# Power.net
KiCad netlist of a schematic drawn in Altium Designer
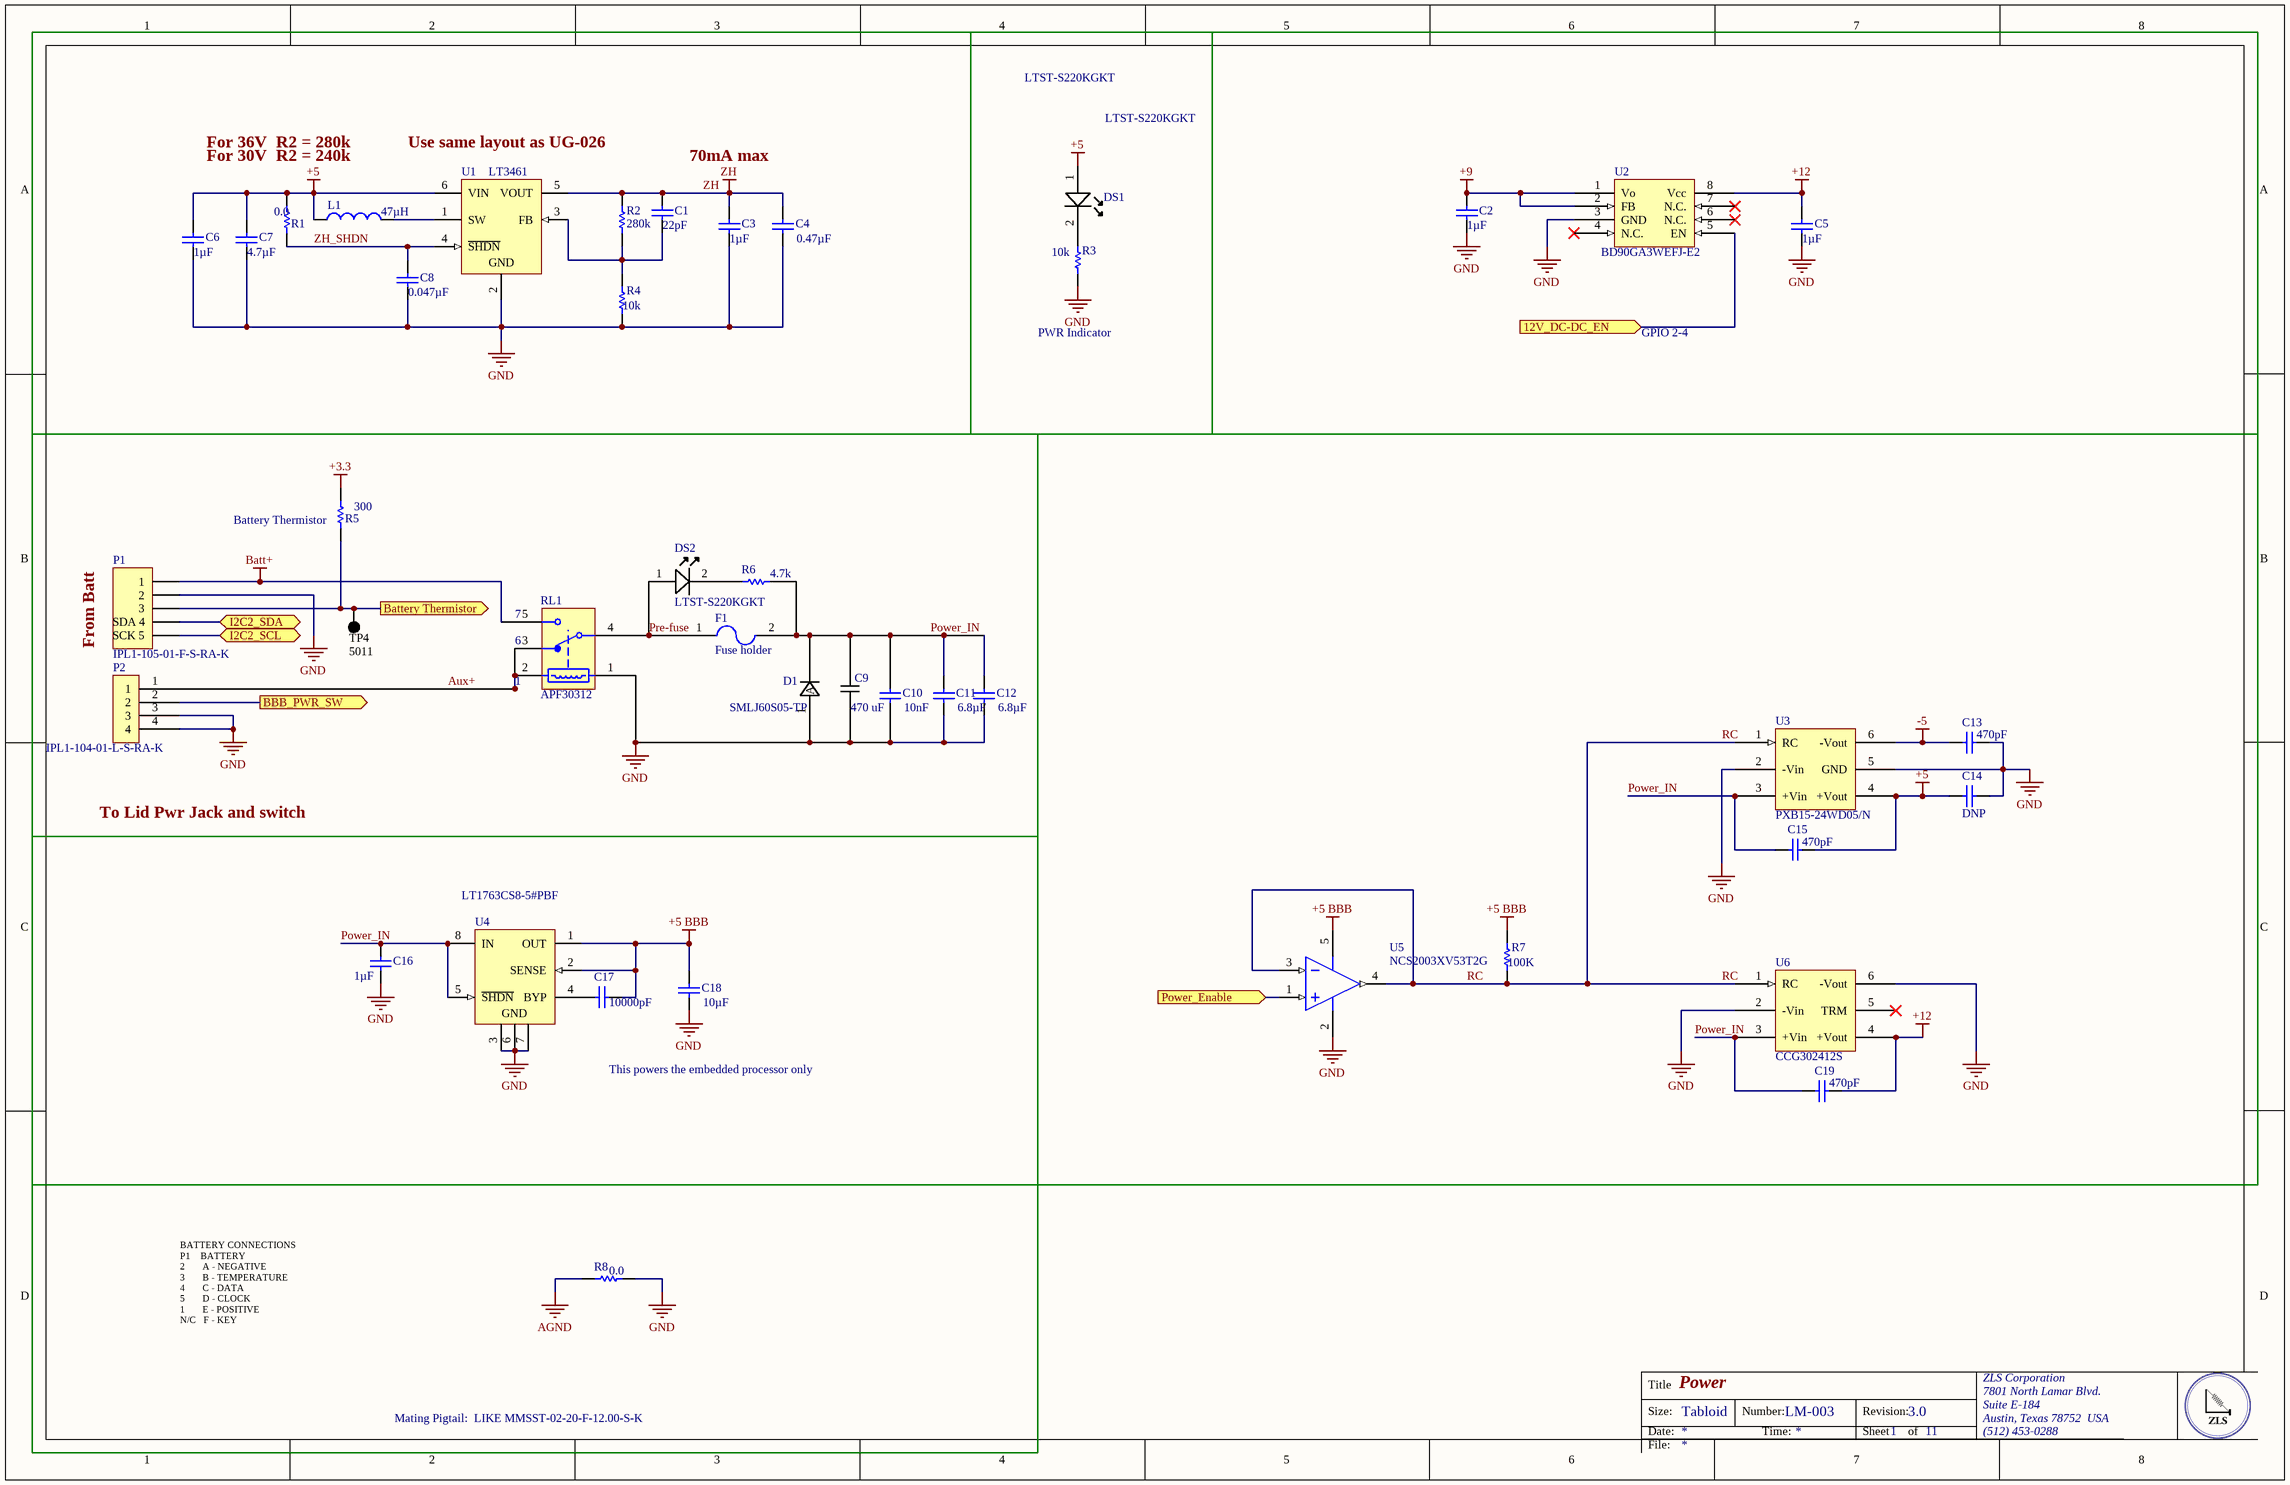
[diagram p0: Power.SchDoc]

(export (version "E")
  (design (tool "Eeschema 10.0.6"))
  (components
    (comp (ref "C1")
      (value "CAP CER 22PF 50V X7R 0603")
      (footprint "CAPC0603(1608)100_N")
      (fields
        (field (name "MANUFACTURER") "AVX Corporation")
        (field (name "MANUFACTURER PART NUMBER") "06035C220JAT2A")
        (field (name "CAPACITANCE") "22pF")
        (field (name "TOLERANCE") "±5%")
      )
      (libsource (lib "Altium Content Vault") (part "CMP-1035-00578-1"))
    )
    (comp (ref "C2")
      (value "CAP CER 1UF 50V X7R 1210")
      (footprint "CAPC1206(3216)130_N")
      (fields
        (field (name "MANUFACTURER") "Murata Electronics North America")
        (field (name "MANUFACTURER PART NUMBER") "GRM32RR71H105KA01L")
        (field (name "CAPACITANCE") "1µF")
        (field (name "TOLERANCE") "±10%")
      )
      (libsource (lib "Altium Content Vault") (part "CMP-1037-04913-1"))
    )
    (comp (ref "C3")
      (value "CAP CER 1UF 50V X7R 1210")
      (footprint "CAPC1210(3225)100_N")
      (fields
        (field (name "MANUFACTURER") "Taiyo Yuden")
        (field (name "MANUFACTURER PART NUMBER") "UMK325B7105KH-T")
        (field (name "CAPACITANCE") "1µF")
        (field (name "TOLERANCE") "±10%")
      )
      (libsource (lib "Altium Content Vault") (part "CMP-1038-01123-1"))
    )
    (comp (ref "C4")
      (value "CAP CER 0.47UF 50V X7R 1206")
      (footprint "CAPC1206(3216)190_N")
      (fields
        (field (name "MANUFACTURER") "Taiyo Yuden")
        (field (name "MANUFACTURER PART NUMBER") "UMK316B7474KL-T")
        (field (name "CAPACITANCE") "0.47µF")
        (field (name "TOLERANCE") "±10%")
      )
      (libsource (lib "Altium Content Vault") (part "CMP-1037-04570-1"))
    )
    (comp (ref "C5")
      (value "CAP CER 1UF 50V X7R 1210")
      (footprint "CAPC1206(3216)130_N")
      (fields
        (field (name "MANUFACTURER") "Murata Electronics North America")
        (field (name "MANUFACTURER PART NUMBER") "GRM32RR71H105KA01L")
        (field (name "CAPACITANCE") "1µF")
        (field (name "TOLERANCE") "±10%")
      )
      (libsource (lib "Altium Content Vault") (part "CMP-1037-04913-1"))
    )
    (comp (ref "C6")
      (value "CAP CER 1UF 16V X7R 0805")
      (footprint "CAPC0805(2012)145_N")
      (fields
        (field (name "MANUFACTURER") "Taiyo Yuden")
        (field (name "MANUFACTURER PART NUMBER") "EMK212B7105KG-T")
        (field (name "CAPACITANCE") "1µF")
        (field (name "TOLERANCE") "±10%")
      )
      (libsource (lib "Altium Content Vault") (part "CMP-1036-04795-1"))
    )
    (comp (ref "C7")
      (value "CAP CER 4.7UF 16V X7R 1206")
      (footprint "CAPC1206(3216)130_N")
      (fields
        (field (name "MANUFACTURER") "Taiyo Yuden")
        (field (name "MANUFACTURER PART NUMBER") "EMK316B7475KL-T")
        (field (name "CAPACITANCE") "4.7µF")
        (field (name "TOLERANCE") "±10%")
      )
      (libsource (lib "Altium Content Vault") (part "CMP-1037-04913-1"))
    )
    (comp (ref "C8")
      (value "CAP CER 0.047UF 16V X7R 0603")
      (footprint "CAPC0805(2012)145_N")
      (fields
        (field (name "MANUFACTURER") "Murata Electronics North America")
        (field (name "MANUFACTURER PART NUMBER") "GRM188R71C473KA01D")
        (field (name "CAPACITANCE") "0.047µF")
        (field (name "TOLERANCE") "±10%")
      )
      (libsource (lib "Altium Content Vault") (part "CMP-1036-04795-1"))
    )
    (comp (ref "C9")
      (value "Aluminum Electrolytic Capacitors - Leaded 16V 470uF 20%")
      (footprint "RAD-0.1")
      (fields (field (name "CAPACITANCE") "470 uF") (field (name "TOLERANCE") "20 %"))
      (libsource (lib "*") (part "CAP B"))
    )
    (comp (ref "C10")
      (value "CAP CER 10000PF 50V X7R 0805")
      (footprint "CAPC0805(2012)145_N")
      (fields
        (field (name "MANUFACTURER") "Kemet")
        (field (name "MANUFACTURER PART NUMBER") "C0805F103K5RACTU")
        (field (name "CAPACITANCE") "10nF")
        (field (name "TOLERANCE") "10%")
      )
      (libsource (lib "Altium Content Vault") (part "CMP-1036-04795-1"))
    )
    (comp (ref "C11")
      (value "CAP CER 6.8UF 50V X5R 1206")
      (footprint "CAPC1210(3225)100_L")
      (fields
        (field (name "MANUFACTURER") "TDK Corporation")
        (field (name "MANUFACTURER PART NUMBER") "C3216X5R1H685K160AB")
        (field (name "CAPACITANCE") "6.8µF")
        (field (name "TOLERANCE") "±10%")
      )
      (libsource (lib "Altium Content Vault") (part "CMP-1038-00632-1"))
    )
    (comp (ref "C12")
      (value "CAP CER 6.8UF 50V X5R 1206")
      (footprint "CAPC1210(3225)100_L")
      (fields
        (field (name "MANUFACTURER") "TDK Corporation")
        (field (name "MANUFACTURER PART NUMBER") "C3216X5R1H685K160AB")
        (field (name "CAPACITANCE") "6.8µF")
        (field (name "TOLERANCE") "±10%")
      )
      (libsource (lib "Altium Content Vault") (part "CMP-1038-00632-1"))
    )
    (comp (ref "C13")
      (value "CAP CER 470PF 3KV X7R 1812")
      (footprint "CAPC1812(4532)230_M")
      (fields
        (field (name "MANUFACTURER") "Kemet")
        (field (name "MANUFACTURER PART NUMBER") "C1812C471KHRACTU")
        (field (name "CAPACITANCE") "470pF")
        (field (name "TOLERANCE") "10%")
      )
      (libsource (lib "Altium Content Vault") (part "CMP-1040-00561-1"))
    )
    (comp (ref "C14")
      (value "DNP")
      (footprint "CAPC1812(4532)230_M")
      (description "CAP CER 470PF 3KV X7R 1812")
      (fields
        (field (name "MANUFACTURER") "Kemet")
        (field (name "MANUFACTURER PART NUMBER") "C1812C471KHRACTU")
      )
      (libsource (lib "Altium Content Vault") (part "CMP-1040-00561-1"))
    )
    (comp (ref "C15")
      (value "CAP CER 470PF 3KV X7R 1812")
      (footprint "CAPC1812(4532)230_M")
      (fields
        (field (name "MANUFACTURER") "Kemet")
        (field (name "MANUFACTURER PART NUMBER") "C1812C471KHRACTU")
        (field (name "CAPACITANCE") "470pF")
        (field (name "TOLERANCE") "10%")
      )
      (libsource (lib "Altium Content Vault") (part "CMP-1040-00561-1"))
    )
    (comp (ref "C16")
      (value "CAP CER 1UF 50V X7R 1210")
      (footprint "CAPC1210(3225)100_L")
      (fields
        (field (name "MANUFACTURER") "Murata Electronics North America")
        (field (name "MANUFACTURER PART NUMBER") "GRM32RR71H105KA01L")
        (field (name "CAPACITANCE") "1µF")
        (field (name "TOLERANCE") "±10%")
      )
      (libsource (lib "Altium Content Vault") (part "CMP-1038-00632-1"))
    )
    (comp (ref "C17")
      (value "CAP CER 10000PF 25V X7R 0805")
      (footprint "CAPC0805(2012)145_N")
      (fields
        (field (name "MANUFACTURER") "Murata Electronics North America")
        (field (name "MANUFACTURER PART NUMBER") "GRM216R71E103KA01D")
        (field (name "CAPACITANCE") "10000pF")
        (field (name "TOLERANCE") "±10%")
      )
      (libsource (lib "Altium Content Vault") (part "CMP-1036-04795-1"))
    )
    (comp (ref "C18")
      (value "CAP CER 10UF 10V X7R 0805")
      (footprint "CAPC0805(2012)145_N")
      (fields
        (field (name "MANUFACTURER") "Murata Electronics North America")
        (field (name "MANUFACTURER PART NUMBER") "GCM21BR71A106KE22L")
        (field (name "CAPACITANCE") "10µF")
        (field (name "TOLERANCE") "±10%")
      )
      (libsource (lib "Altium Content Vault") (part "CMP-1036-04795-1"))
    )
    (comp (ref "C19")
      (value "CAP CER 470PF 3KV X7R 1812")
      (footprint "CAPC1812(4532)230_M")
      (fields
        (field (name "MANUFACTURER") "Kemet")
        (field (name "MANUFACTURER PART NUMBER") "C1812C471KHRACTU")
        (field (name "CAPACITANCE") "470pF")
        (field (name "TOLERANCE") "10%")
      )
      (libsource (lib "Altium Content Vault") (part "CMP-1040-00561-1"))
    )
    (comp (ref "D1")
      (value "DIODE GEN PURP 50V 6A DO214AB")
      (footprint "DO-214AB")
      (fields
        (field (name "MANUFACTURER") "Micro Commercial Co")
        (field (name "MANUFACTURER PART NUMBER") "SMLJ60S05-TP")
      )
      (libsource (lib "*") (part "DIODE A/K A"))
    )
    (comp (ref "DS1")
      (value "Lite-On LTST-S220KGKT Green LED, 571 nm 2012 (0805) Side View, Rectangle Lens SMD package")
      (footprint "0805C_L")
      (fields
        (field (name "MANUFACTURER") "Vishay / Lite-On")
        (field (name "MANUFACTURER PART NUMBER") "LTST-S220KGKT")
      )
      (libsource (lib "*") (part "LED A/K"))
    )
    (comp (ref "DS2")
      (value "Lite-On LTST-S220KGKT Green LED, 571 nm 2012 (0805) Side View, Rectangle Lens SMD package")
      (footprint "0805C_L")
      (fields
        (field (name "MANUFACTURER") "Vishay / Lite-On")
        (field (name "MANUFACTURER PART NUMBER") "LTST-S220KGKT")
      )
      (libsource (lib "*") (part "LED A/K"))
    )
    (comp (ref "F1")
      (value "Fuse holder")
      (footprint "01530007Z")
      (description "FUSE HOLDER BLADE 32V 15A PCB")
      (fields (field (name "VOLTAGE") "32V"))
      (libsource (lib "Miscellaneous Devices") (part "Fuse 2"))
    )
    (comp (ref "L1")
      (value "FIXED IND 47UH 170MA 1.3 OHM SMD")
      (footprint "0402-A")
      (fields (field (name "INDUCTANCE") "47µH") (field (name "TOLERANCE") "±10%"))
      (libsource (lib "Miscellaneous Devices") (part "Inductor"))
    )
    (comp (ref "P1")
      (value "IPL1-105-01-F-S-RA-K")
      (footprint "IPL1-105-1")
      (description "Header, 5-Pin, Right Angle")
      (libsource (lib "Miscellaneous Connectors") (part "Header 5H"))
    )
    (comp (ref "P2")
      (value "IPL1-104-01-L-S-RA-K")
      (footprint "IPL1-104-01")
      (description ".100 TERMINAL ASSY")
      (libsource (lib "ZLS_LIB") (part "53047-0410"))
    )
    (comp (ref "R1")
      (value "RES SMD 0.0 OHM JUMPER 1/8W 0805")
      (footprint "RESC0805(2012)_M")
      (fields
        (field (name "MANUFACTURER") "Vishay Dale")
        (field (name "MANUFACTURER PART NUMBER") "CRCW08050000Z0EA")
        (field (name "RESISTANCE (OHMS)") "0.0")
        (field (name "TOLERANCE") "Jumper")
      )
      (libsource (lib "Altium Content Vault") (part "CMP-1013-00017-1"))
    )
    (comp (ref "R2")
      (value "RES SMD 280K OHM 1% 1/8W 0805")
      (footprint "RESC0805(2012)_M")
      (fields
        (field (name "MANUFACTURER") "Vishay Dale")
        (field (name "MANUFACTURER PART NUMBER") "CRCW0805280KFKEA")
        (field (name "RESISTANCE (OHMS)") "280k")
        (field (name "TOLERANCE") "±1%")
      )
      (libsource (lib "Altium Content Vault") (part "CMP-1013-00017-1"))
    )
    (comp (ref "R3")
      (value "RES SMD 10K OHM 1% 1/8W 0805")
      (footprint "RESC0805(2012)_M")
      (fields
        (field (name "MANUFACTURER") "Vishay Dale")
        (field (name "MANUFACTURER PART NUMBER") "CRCW080510K0FKTA")
        (field (name "RESISTANCE (OHMS)") "10k")
        (field (name "TOLERANCE") "±1%")
      )
      (libsource (lib "Altium Content Vault") (part "CMP-1013-00017-1"))
    )
    (comp (ref "R4")
      (value "RES SMD 10K OHM 1% 1/8W 0805")
      (footprint "RESC0805(2012)_M")
      (fields
        (field (name "MANUFACTURER") "Yageo")
        (field (name "MANUFACTURER PART NUMBER") "RC0805FR-0710KL")
        (field (name "RESISTANCE (OHMS)") "10k")
        (field (name "TOLERANCE") "±1%")
      )
      (libsource (lib "Altium Content Vault") (part "CMP-1013-00017-1"))
    )
    (comp (ref "R5")
      (value "300K 5% 0805(2012)")
      (footprint "RESC0805(2012)_M")
      (description "300K 0.125W 5% 0805 (2012 Metric)  SMD")
      (fields
        (field (name "MANUFACTURER") "Vishay Dale")
        (field (name "MANUFACTURER PART NUMBER") "CRCW0805300RFKEA")
        (field (name "RESISTANCE (OHMS)") "300")
      )
      (libsource (lib "Altium Content Vault") (part "CMP-1013-00133-1"))
    )
    (comp (ref "R6")
      (value "RES SMD 4.7K OHM 1% 1/8W 0805")
      (footprint "RESC0805(2012)_M")
      (fields
        (field (name "MANUFACTURER") "Vishay Dale")
        (field (name "MANUFACTURER PART NUMBER") "CRCW08054K70FKEA")
        (field (name "RESISTANCE (OHMS)") "4.7k")
        (field (name "TOLERANCE") "±1%")
      )
      (libsource (lib "Altium Content Vault") (part "CMP-1013-00017-1"))
    )
    (comp (ref "R7")
      (value "RES SMD 100K OHM 1% 1/8W 0805")
      (footprint "RESC0805(2012)_M")
      (fields
        (field (name "MANUFACTURER") "Vishay")
        (field (name "MANUFACTURER PART NUMBER") "CRCW0805100KFKEA")
        (field (name "TOLERANCE") "1%")
        (field (name "RESISTANCE") "100K")
      )
      (libsource (lib "Altium Content Vault") (part "CMP-1013-00017-1"))
    )
    (comp (ref "R8")
      (value "RES SMD 0.0 OHM JUMPER 1/8W 0805")
      (footprint "RESC0805(2012)_M")
      (fields
        (field (name "MANUFACTURER") "Vishay Dale")
        (field (name "MANUFACTURER PART NUMBER") "CRCW08050000Z0EA")
        (field (name "RESISTANCE (OHMS)") "0.0")
        (field (name "TOLERANCE") "Jumper")
      )
      (libsource (lib "Altium Content Vault") (part "CMP-1013-00017-1"))
    )
    (comp (ref "RL1")
      (value "APF30312")
      (footprint "PNSC-PF-5-2800x500x1500_V")
      (fields (field (name "MANUFACTURER") "Panasonic"))
      (libsource (lib "Altium Content Vault") (part "CMP-1503-00270-1"))
    )
    (comp (ref "TP4")
      (value "5011")
      (footprint "KSTN-5011_V")
      (description "Test Point, Black, Through Hole, RoHS, Bulk")
      (fields (field (name "MANUFACTURER") "Keystone"))
      (libsource (lib "Altium Content Vault") (part "CMP-1672-00003-4"))
    )
    (comp (ref "U1")
      (value "LT3461")
      (footprint "LT-S6-6-TSOT-23_N")
      (description "IC REG BOOST ADJ 0.3A TSOT23-6")
      (libsource (lib "Altium Content Vault") (part "CMP-0491-01698-1"))
    )
    (comp (ref "U2")
      (value "BD90GA3WEFJ-E2")
      (footprint "TSOP127P600X100-8N")
      (description "IC REG LDO 9V 0.3A 8HTSOP-J")
      (fields
        (field (name "MANUFACTURER") "Rohm Semiconductor")
        (field (name "MANUFACTURER PART NUMBER") "BD90GA3WEFJ-E2")
      )
      (libsource (lib "ZLS_Schematic_lib") (part "BD90GA3WEFJ-E2"))
    )
    (comp (ref "U3")
      (value "PXB15-24WD05/N")
      (footprint "PXB15-24WD05/N")
      (description "IC CONV DC-DC 15W DUAL 5V PCB")
      (libsource (lib "ZLS_LIB") (part "CCG302412S"))
    )
    (comp (ref "U4")
      (value "LT1763CS8-5#PBF")
      (footprint "LT-S8-8_M")
      (fields (field (name "MANUFACTURER") "Linear Technology"))
      (libsource (lib "Altium Content Vault") (part "LT-LT1763-S8-8"))
    )
    (comp (ref "U5")
      (value "NCS2003XV53T2G")
      (footprint "ONSC-SOT-553-5-463B_V")
      (fields (field (name "MANUFACTURER") "On Semiconductor"))
      (libsource (lib "Altium Content Vault") (part "ONSC-NCS200X-5"))
    )
    (comp (ref "U6")
      (value "CCG302412S")
      (footprint "CCG30")
      (description "DC/DC CONVERTER 12V 2.5A PCB")
      (libsource (lib "") (part "CCG302412S_1"))
    )
  )
  (nets
    (net (code "1") (name "+3.3") (class "Default")
      (node (ref "R5") (pin "2") (pinfunction "2_2") (pintype "passive"))
    )
    (net (code "2") (name "+5") (class "Default")
      (node (ref "C14") (pin "1") (pinfunction "1_1") (pintype "passive"))
      (node (ref "C15") (pin "2") (pinfunction "2_2") (pintype "passive"))
      (node (ref "C6") (pin "2") (pinfunction "2_2") (pintype "passive"))
      (node (ref "C7") (pin "2") (pinfunction "2_2") (pintype "passive"))
      (node (ref "DS1") (pin "1") (pinfunction "A_1") (pintype "passive"))
      (node (ref "L1") (pin "1") (pinfunction "1_1") (pintype "passive"))
      (node (ref "R1") (pin "1") (pinfunction "1_1") (pintype "passive"))
      (node (ref "U1") (pin "6") (pinfunction "VIN_6") (pintype "power_in"))
      (node (ref "U3") (pin "4") (pinfunction "+Vout_4") (pintype "power_in"))
    )
    (net (code "3") (name "+5 BBB") (class "Default")
      (node (ref "C17") (pin "1") (pinfunction "1_1") (pintype "passive"))
      (node (ref "C18") (pin "2") (pinfunction "2_2") (pintype "passive"))
      (node (ref "R7") (pin "1") (pinfunction "1_1") (pintype "passive"))
      (node (ref "U4") (pin "1") (pinfunction "OUT_1") (pintype "power_in"))
      (node (ref "U4") (pin "2") (pinfunction "SENSE_2") (pintype "input"))
      (node (ref "U5") (pin "5") (pinfunction "VDD_5") (pintype "power_in"))
    )
    (net (code "4") (name "+9") (class "Default")
      (node (ref "C2") (pin "2") (pinfunction "2_2") (pintype "passive"))
      (node (ref "U2") (pin "1") (pinfunction "Vo_1") (pintype "power_in"))
      (node (ref "U2") (pin "2") (pinfunction "FB_2") (pintype "input"))
    )
    (net (code "5") (name "+12") (class "Default")
      (node (ref "C19") (pin "2") (pinfunction "2_2") (pintype "passive"))
      (node (ref "C5") (pin "2") (pinfunction "2_2") (pintype "passive"))
      (node (ref "U2") (pin "8") (pinfunction "Vcc_8") (pintype "power_in"))
      (node (ref "U6") (pin "4") (pinfunction "+Vout_4") (pintype "power_in"))
    )
    (net (code "6") (name "-5") (class "Default")
      (node (ref "C13") (pin "1") (pinfunction "1_1") (pintype "passive"))
      (node (ref "U3") (pin "6") (pinfunction "-Vout_6") (pintype "power_in"))
    )
    (net (code "7") (name "/12V_DC-DC_EN") (class "Default")
      (node (ref "U2") (pin "5") (pinfunction "EN_5") (pintype "input"))
    )
    (net (code "8") (name "/Aux+") (class "Default")
      (node (ref "P2") (pin "1") (pinfunction "1_1") (pintype "passive"))
      (node (ref "RL1") (pin "2") (pinfunction "2_2") (pintype "passive"))
      (node (ref "RL1") (pin "3") (pinfunction "NC_3") (pintype "passive"))
    )
    (net (code "9") (name "/BBB_PWR_SW") (class "Default")
      (node (ref "P2") (pin "2") (pinfunction "2_2") (pintype "passive"))
    )
    (net (code "10") (name "/Battery Thermistor") (class "Default")
      (node (ref "P1") (pin "3") (pinfunction "3_3") (pintype "passive"))
      (node (ref "R5") (pin "1") (pinfunction "1_1") (pintype "passive"))
      (node (ref "TP4") (pin "1") (pinfunction "1_1") (pintype "passive"))
    )
    (net (code "11") (name "/I2C2_SCL") (class "Default")
      (node (ref "P1") (pin "5") (pinfunction "SCK_5_5") (pintype "passive"))
    )
    (net (code "12") (name "/I2C2_SDA") (class "Default")
      (node (ref "P1") (pin "4") (pinfunction "SDA_4_4") (pintype "passive"))
    )
    (net (code "13") (name "/Power_Enable") (class "Default")
      (node (ref "U5") (pin "1") (pinfunction "IN+_1") (pintype "input"))
    )
    (net (code "14") (name "/Power_IN") (class "Default")
      (node (ref "C10") (pin "2") (pinfunction "2_2") (pintype "passive"))
      (node (ref "C11") (pin "2") (pinfunction "2_2") (pintype "passive"))
      (node (ref "C12") (pin "2") (pinfunction "2_2") (pintype "passive"))
      (node (ref "C15") (pin "1") (pinfunction "1_1") (pintype "passive"))
      (node (ref "C16") (pin "2") (pinfunction "2_2") (pintype "passive"))
      (node (ref "C19") (pin "1") (pinfunction "1_1") (pintype "passive"))
      (node (ref "C9") (pin "1") (pinfunction "1_1") (pintype "passive"))
      (node (ref "D1") (pin "2") (pinfunction "K_2") (pintype "passive"))
      (node (ref "F1") (pin "2") (pinfunction "2_2") (pintype "passive"))
      (node (ref "R6") (pin "1") (pinfunction "1_1") (pintype "passive"))
      (node (ref "U3") (pin "3") (pinfunction "+Vin_3") (pintype "power_in"))
      (node (ref "U4") (pin "5") (pinfunction "~{SHDN}_5") (pintype "input"))
      (node (ref "U4") (pin "8") (pinfunction "IN_8") (pintype "power_in"))
      (node (ref "U6") (pin "3") (pinfunction "+Vin_3") (pintype "passive"))
    )
    (net (code "15") (name "/Pre-fuse") (class "Default")
      (node (ref "DS2") (pin "1") (pinfunction "A_1") (pintype "passive"))
      (node (ref "F1") (pin "1") (pinfunction "1_1") (pintype "passive"))
      (node (ref "RL1") (pin "4") (pinfunction "COM_4") (pintype "passive"))
    )
    (net (code "16") (name "/RC") (class "Default")
      (node (ref "R7") (pin "2") (pinfunction "2_2") (pintype "passive"))
      (node (ref "U3") (pin "1") (pinfunction "RC_1") (pintype "input"))
      (node (ref "U5") (pin "3") (pinfunction "IN-_3") (pintype "input"))
      (node (ref "U5") (pin "4") (pinfunction "OUT_4") (pintype "output"))
      (node (ref "U6") (pin "1") (pinfunction "RC_1") (pintype "input"))
    )
    (net (code "17") (name "/ZH_SHDN") (class "Default")
      (node (ref "C8") (pin "2") (pinfunction "2_2") (pintype "passive"))
      (node (ref "R1") (pin "2") (pinfunction "2_2") (pintype "passive"))
      (node (ref "U1") (pin "4") (pinfunction "~{SHDN}_4") (pintype "input"))
    )
    (net (code "18") (name "AGND") (class "Default")
      (node (ref "R8") (pin "2") (pinfunction "2_2") (pintype "passive"))
    )
    (net (code "19") (name "Batt+") (class "Default")
      (node (ref "P1") (pin "1") (pinfunction "1_1") (pintype "passive"))
      (node (ref "RL1") (pin "5") (pinfunction "NO_5") (pintype "passive"))
    )
    (net (code "20") (name "GND") (class "Default")
      (node (ref "C10") (pin "1") (pinfunction "1_1") (pintype "passive"))
      (node (ref "C11") (pin "1") (pinfunction "1_1") (pintype "passive"))
      (node (ref "C12") (pin "1") (pinfunction "1_1") (pintype "passive"))
      (node (ref "C13") (pin "2") (pinfunction "2_2") (pintype "passive"))
      (node (ref "C14") (pin "2") (pinfunction "2_2") (pintype "passive"))
      (node (ref "C16") (pin "1") (pinfunction "1_1") (pintype "passive"))
      (node (ref "C18") (pin "1") (pinfunction "1_1") (pintype "passive"))
      (node (ref "C2") (pin "1") (pinfunction "1_1") (pintype "passive"))
      (node (ref "C3") (pin "1") (pinfunction "1_1") (pintype "passive"))
      (node (ref "C4") (pin "1") (pinfunction "1_1") (pintype "passive"))
      (node (ref "C5") (pin "1") (pinfunction "1_1") (pintype "passive"))
      (node (ref "C6") (pin "1") (pinfunction "1_1") (pintype "passive"))
      (node (ref "C7") (pin "1") (pinfunction "1_1") (pintype "passive"))
      (node (ref "C8") (pin "1") (pinfunction "1_1") (pintype "passive"))
      (node (ref "C9") (pin "2") (pinfunction "2_2") (pintype "passive"))
      (node (ref "D1") (pin "1") (pinfunction "A_1") (pintype "passive"))
      (node (ref "P1") (pin "2") (pinfunction "2_2") (pintype "passive"))
      (node (ref "P2") (pin "3") (pinfunction "3_3") (pintype "passive"))
      (node (ref "P2") (pin "4") (pinfunction "4_4") (pintype "passive"))
      (node (ref "R3") (pin "1") (pinfunction "1_1") (pintype "passive"))
      (node (ref "R4") (pin "2") (pinfunction "2_2") (pintype "passive"))
      (node (ref "R8") (pin "1") (pinfunction "1_1") (pintype "passive"))
      (node (ref "RL1") (pin "1") (pinfunction "1_1") (pintype "passive"))
      (node (ref "U1") (pin "2") (pinfunction "GND_2") (pintype "power_in"))
      (node (ref "U2") (pin "3") (pinfunction "GND_3") (pintype "power_in"))
      (node (ref "U3") (pin "2") (pinfunction "-Vin_2") (pintype "power_in"))
      (node (ref "U3") (pin "5") (pinfunction "GND_5") (pintype "power_in"))
      (node (ref "U4") (pin "3") (pinfunction "GND_3") (pintype "power_in"))
      (node (ref "U4") (pin "6") (pinfunction "GND_6") (pintype "power_in"))
      (node (ref "U4") (pin "7") (pinfunction "GND_7") (pintype "power_in"))
      (node (ref "U5") (pin "2") (pinfunction "VSS_2") (pintype "power_in"))
      (node (ref "U6") (pin "2") (pinfunction "-Vin_2") (pintype "power_in"))
      (node (ref "U6") (pin "6") (pinfunction "-Vout_6") (pintype "power_in"))
    )
    (net (code "21") (name "Net-(DS1-K)") (class "Default")
      (node (ref "DS1") (pin "2") (pinfunction "K_2") (pintype "passive"))
      (node (ref "R3") (pin "2") (pinfunction "2_2") (pintype "passive"))
    )
    (net (code "22") (name "Net-(DS2-K)") (class "Default")
      (node (ref "DS2") (pin "2") (pinfunction "K_2") (pintype "passive"))
      (node (ref "R6") (pin "2") (pinfunction "2_2") (pintype "passive"))
    )
    (net (code "23") (name "Net-(U1-FB)") (class "Default")
      (node (ref "C1") (pin "1") (pinfunction "1_1") (pintype "passive"))
      (node (ref "R2") (pin "2") (pinfunction "2_2") (pintype "passive"))
      (node (ref "R4") (pin "1") (pinfunction "1_1") (pintype "passive"))
      (node (ref "U1") (pin "3") (pinfunction "FB_3") (pintype "input"))
    )
    (net (code "24") (name "Net-(U1-SW)") (class "Default")
      (node (ref "L1") (pin "2") (pinfunction "2_2") (pintype "passive"))
      (node (ref "U1") (pin "1") (pinfunction "SW_1") (pintype "passive"))
    )
    (net (code "25") (name "Net-(U4-BYP)") (class "Default")
      (node (ref "C17") (pin "2") (pinfunction "2_2") (pintype "passive"))
      (node (ref "U4") (pin "4") (pinfunction "BYP_4") (pintype "passive"))
    )
    (net (code "26") (name "ZH") (class "Default")
      (node (ref "C1") (pin "2") (pinfunction "2_2") (pintype "passive"))
      (node (ref "C3") (pin "2") (pinfunction "2_2") (pintype "passive"))
      (node (ref "C4") (pin "2") (pinfunction "2_2") (pintype "passive"))
      (node (ref "R2") (pin "1") (pinfunction "1_1") (pintype "passive"))
      (node (ref "U1") (pin "5") (pinfunction "VOUT_5") (pintype "power_in"))
    )
    (net (code "27") (name "unconnected-(U2-N.C.-Pad4)") (class "Default")
      (node (ref "U2") (pin "4") (pinfunction "N.C._4") (pintype "input+no_connect"))
    )
    (net (code "28") (name "unconnected-(U2-N.C.-Pad6)") (class "Default")
      (node (ref "U2") (pin "6") (pinfunction "N.C._6") (pintype "input+no_connect"))
    )
    (net (code "29") (name "unconnected-(U2-N.C.-Pad7)") (class "Default")
      (node (ref "U2") (pin "7") (pinfunction "N.C._7") (pintype "input+no_connect"))
    )
    (net (code "30") (name "unconnected-(U6-TRM-Pad5)") (class "Default")
      (node (ref "U6") (pin "5") (pinfunction "TRM_5") (pintype "passive+no_connect"))
    )
  )
)
